# AUDIO_AMP.net
KiCad netlist of a schematic drawn in Altium Designer
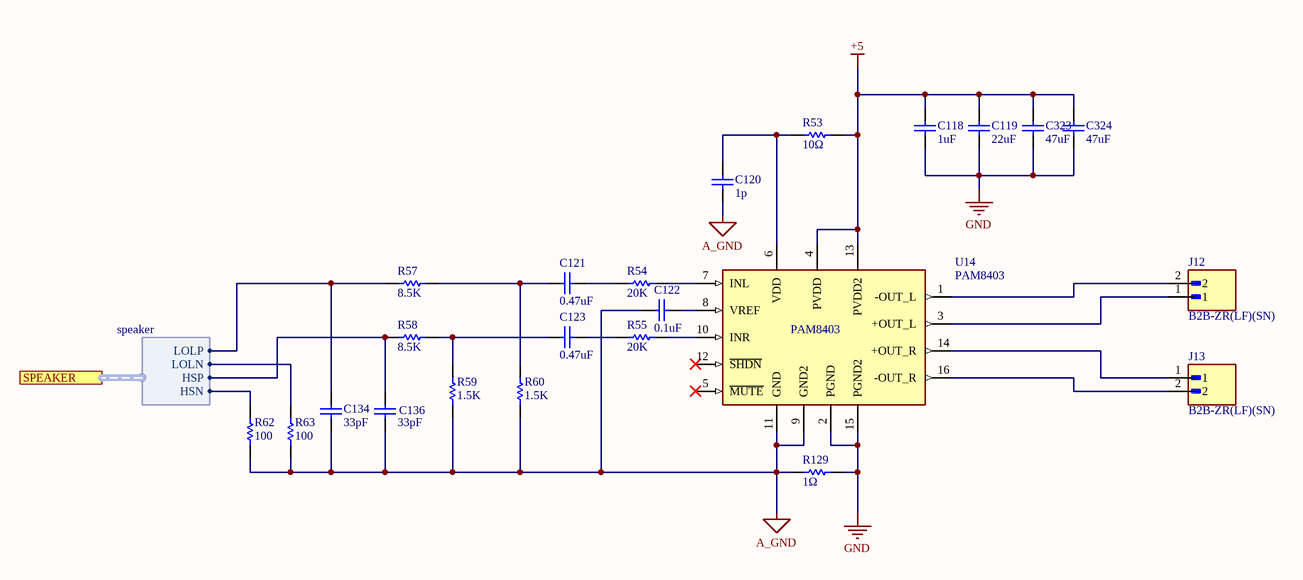
[diagram p0: AUDIO_AMP.SchDoc]

(export (version "E")
  (design (tool "Eeschema 10.0.6"))
  (components
    (comp (ref "C118")
      (value "1uF")
      (footprint "C0805")
      (fields (field (name "Comment") "C0805"))
      (libsource (lib "kit") (part "C0805"))
    )
    (comp (ref "C119")
      (value "22uF")
      (footprint "C1210")
      (fields (field (name "Comment") "C1210"))
      (libsource (lib "kit") (part "C1210"))
    )
    (comp (ref "C120")
      (value "1p")
      (footprint "C0402")
      (fields (field (name "Comment") "C0402"))
      (libsource (lib "kit") (part "C0402"))
    )
    (comp (ref "C121")
      (value "0.47uF")
      (footprint "C0603")
      (fields (field (name "Comment") "C0603"))
      (libsource (lib "kit") (part "C0603"))
    )
    (comp (ref "C122")
      (value "0.1uF")
      (footprint "C0603")
      (fields (field (name "Comment") "C0603"))
      (libsource (lib "kit") (part "C0603"))
    )
    (comp (ref "C123")
      (value "0.47uF")
      (footprint "C0603")
      (fields (field (name "Comment") "C0603"))
      (libsource (lib "kit") (part "C0603"))
    )
    (comp (ref "C134")
      (value "33pF")
      (footprint "C0402")
      (fields (field (name "Comment") "C0402"))
      (libsource (lib "kit") (part "C0402"))
    )
    (comp (ref "C136")
      (value "33pF")
      (footprint "C0402")
      (fields (field (name "Comment") "C0402"))
      (libsource (lib "kit") (part "C0402"))
    )
    (comp (ref "C323")
      (value "47uF")
      (footprint "C1812")
      (fields (field (name "Comment") "C1812"))
      (libsource (lib "kit") (part "C1812"))
    )
    (comp (ref "C324")
      (value "47uF")
      (footprint "C1812")
      (fields (field (name "Comment") "C1812"))
      (libsource (lib "kit") (part "C1812"))
    )
    (comp (ref "J12")
      (value "B2B-ZR(LF)(SN)")
      (footprint "JST_B2B-ZR(LF)(SN)")
      (description "Connector Header Through Hole 2 position 0.059 (1.50mm)")
      (libsource (lib "kit") (part "B2B-ZR(LF)(SN)"))
    )
    (comp (ref "J13")
      (value "B2B-ZR(LF)(SN)")
      (footprint "JST_B2B-ZR(LF)(SN)")
      (description "Connector Header Through Hole 2 position 0.059 (1.50mm)")
      (libsource (lib "") (part "B2B-ZR(LF)(SN)_1"))
    )
    (comp (ref "R53")
      (value "10Ω")
      (footprint "R0603")
      (fields (field (name "Comment") "R0603"))
      (libsource (lib "kit") (part "R0603"))
    )
    (comp (ref "R54")
      (value "20K")
      (footprint "R0603")
      (fields (field (name "Comment") "R0603"))
      (libsource (lib "kit") (part "R0603"))
    )
    (comp (ref "R55")
      (value "20K")
      (footprint "R0603")
      (fields (field (name "Comment") "R0603"))
      (libsource (lib "kit") (part "R0603"))
    )
    (comp (ref "R57")
      (value "8.5K")
      (footprint "R0603")
      (fields (field (name "Comment") "R0603"))
      (libsource (lib "kit") (part "R0603"))
    )
    (comp (ref "R58")
      (value "8.5K")
      (footprint "R0603")
      (fields (field (name "Comment") "R0603"))
      (libsource (lib "kit") (part "R0603"))
    )
    (comp (ref "R59")
      (value "1.5K")
      (footprint "R0603")
      (fields (field (name "Comment") "R0603"))
      (libsource (lib "kit") (part "R0603"))
    )
    (comp (ref "R60")
      (value "1.5K")
      (footprint "R0603")
      (fields (field (name "Comment") "R0603"))
      (libsource (lib "kit") (part "R0603"))
    )
    (comp (ref "R62")
      (value "100")
      (footprint "R0603")
      (fields (field (name "Comment") "R0603"))
      (libsource (lib "kit") (part "R0603"))
    )
    (comp (ref "R63")
      (value "100")
      (footprint "R0603")
      (fields (field (name "Comment") "R0603"))
      (libsource (lib "kit") (part "R0603"))
    )
    (comp (ref "R129")
      (value "1Ω")
      (footprint "R0603")
      (fields (field (name "Comment") "R0603"))
      (libsource (lib "kit") (part "R0603"))
    )
    (comp (ref "U14")
      (value "PAM8403")
      (footprint "SOP-16")
      (description "Audio Amp Speaker 2-CH Stereo 3.2W Class-D 16-Pin SOP T/R")
      (libsource (lib "kit") (part "PAM8403"))
    )
  )
  (nets
    (net (code "2") (name "+5") (class "Default")
      (node (ref "C118") (pin "1") (pinfunction "1_1") (pintype "passive"))
      (node (ref "C119") (pin "2") (pinfunction "2_2") (pintype "passive"))
      (node (ref "C323") (pin "2") (pinfunction "2_2") (pintype "passive"))
      (node (ref "C324") (pin "2") (pinfunction "2_2") (pintype "passive"))
      (node (ref "R53") (pin "2") (pinfunction "2_2") (pintype "passive"))
      (node (ref "U14") (pin "13") (pinfunction "PVDD2_13") (pintype "power_in"))
      (node (ref "U14") (pin "4") (pinfunction "PVDD_4") (pintype "power_in"))
    )
    (net (code "3") (name "/HSN") (class "Default")
      (node (ref "R62") (pin "2") (pinfunction "2_2") (pintype "passive"))
    )
    (net (code "4") (name "/HSP") (class "Default")
      (node (ref "C136") (pin "2") (pinfunction "2_2") (pintype "passive"))
      (node (ref "R58") (pin "1") (pinfunction "1_1") (pintype "passive"))
    )
    (net (code "5") (name "/LOLN") (class "Default")
      (node (ref "R63") (pin "2") (pinfunction "2_2") (pintype "passive"))
    )
    (net (code "6") (name "/LOLP") (class "Default")
      (node (ref "C134") (pin "2") (pinfunction "2_2") (pintype "passive"))
      (node (ref "R57") (pin "1") (pinfunction "1_1") (pintype "passive"))
    )
    (net (code "8") (name "A_GND") (class "Default")
      (node (ref "C120") (pin "1") (pinfunction "1_1") (pintype "passive"))
      (node (ref "C122") (pin "2") (pinfunction "2_2") (pintype "passive"))
      (node (ref "C134") (pin "1") (pinfunction "1_1") (pintype "passive"))
      (node (ref "C136") (pin "1") (pinfunction "1_1") (pintype "passive"))
      (node (ref "R129") (pin "1") (pinfunction "1_1") (pintype "passive"))
      (node (ref "R59") (pin "1") (pinfunction "1_1") (pintype "passive"))
      (node (ref "R60") (pin "1") (pinfunction "1_1") (pintype "passive"))
      (node (ref "R62") (pin "1") (pinfunction "1_1") (pintype "passive"))
      (node (ref "R63") (pin "1") (pinfunction "1_1") (pintype "passive"))
      (node (ref "U14") (pin "11") (pinfunction "GND_11") (pintype "power_in"))
      (node (ref "U14") (pin "9") (pinfunction "GND2_9") (pintype "power_in"))
    )
    (net (code "9") (name "GND") (class "Default")
      (node (ref "C118") (pin "2") (pinfunction "2_2") (pintype "passive"))
      (node (ref "C119") (pin "1") (pinfunction "1_1") (pintype "passive"))
      (node (ref "C323") (pin "1") (pinfunction "1_1") (pintype "passive"))
      (node (ref "C324") (pin "1") (pinfunction "1_1") (pintype "passive"))
      (node (ref "R129") (pin "2") (pinfunction "2_2") (pintype "passive"))
      (node (ref "U14") (pin "15") (pinfunction "PGND2_15") (pintype "power_in"))
      (node (ref "U14") (pin "2") (pinfunction "PGND_2") (pintype "power_in"))
    )
    (net (code "10") (name "Net-(C121-Pad1)") (class "Default")
      (node (ref "C121") (pin "1") (pinfunction "1_1") (pintype "passive"))
      (node (ref "R54") (pin "1") (pinfunction "1_1") (pintype "passive"))
    )
    (net (code "11") (name "Net-(C121-Pad2)") (class "Default")
      (node (ref "C121") (pin "2") (pinfunction "2_2") (pintype "passive"))
      (node (ref "R57") (pin "2") (pinfunction "2_2") (pintype "passive"))
      (node (ref "R60") (pin "2") (pinfunction "2_2") (pintype "passive"))
    )
    (net (code "12") (name "Net-(C123-Pad1)") (class "Default")
      (node (ref "C123") (pin "1") (pinfunction "1_1") (pintype "passive"))
      (node (ref "R55") (pin "1") (pinfunction "1_1") (pintype "passive"))
    )
    (net (code "13") (name "Net-(C123-Pad2)") (class "Default")
      (node (ref "C123") (pin "2") (pinfunction "2_2") (pintype "passive"))
      (node (ref "R58") (pin "2") (pinfunction "2_2") (pintype "passive"))
      (node (ref "R59") (pin "2") (pinfunction "2_2") (pintype "passive"))
    )
    (net (code "14") (name "Net-(U14-+OUT_L)") (class "Default")
      (node (ref "J12") (pin "1") (pinfunction "1_1") (pintype "passive"))
      (node (ref "U14") (pin "3") (pinfunction "+OUT_L_3") (pintype "output"))
    )
    (net (code "15") (name "Net-(U14-+OUT_R)") (class "Default")
      (node (ref "J13") (pin "1") (pinfunction "1_1") (pintype "passive"))
      (node (ref "U14") (pin "14") (pinfunction "+OUT_R_14") (pintype "output"))
    )
    (net (code "16") (name "Net-(U14--OUT_L)") (class "Default")
      (node (ref "J12") (pin "2") (pinfunction "2_2") (pintype "passive"))
      (node (ref "U14") (pin "1") (pinfunction "-OUT_L_1") (pintype "output"))
    )
    (net (code "17") (name "Net-(U14--OUT_R)") (class "Default")
      (node (ref "J13") (pin "2") (pinfunction "2_2") (pintype "passive"))
      (node (ref "U14") (pin "16") (pinfunction "-OUT_R_16") (pintype "output"))
    )
    (net (code "18") (name "Net-(U14-INL)") (class "Default")
      (node (ref "R54") (pin "2") (pinfunction "2_2") (pintype "passive"))
      (node (ref "U14") (pin "7") (pinfunction "INL_7") (pintype "input"))
    )
    (net (code "19") (name "Net-(U14-INR)") (class "Default")
      (node (ref "R55") (pin "2") (pinfunction "2_2") (pintype "passive"))
      (node (ref "U14") (pin "10") (pinfunction "INR_10") (pintype "input"))
    )
    (net (code "20") (name "Net-(U14-VDD)") (class "Default")
      (node (ref "C120") (pin "2") (pinfunction "2_2") (pintype "passive"))
      (node (ref "R53") (pin "1") (pinfunction "1_1") (pintype "passive"))
      (node (ref "U14") (pin "6") (pinfunction "VDD_6") (pintype "power_in"))
    )
    (net (code "21") (name "Net-(U14-VREF)") (class "Default")
      (node (ref "C122") (pin "1") (pinfunction "1_1") (pintype "passive"))
      (node (ref "U14") (pin "8") (pinfunction "VREF_8") (pintype "input"))
    )
    (net (code "22") (name "unconnected-(U14-~{MUTE}-Pad5)") (class "Default")
      (node (ref "U14") (pin "5") (pinfunction "~{MUTE}_5") (pintype "input+no_connect"))
    )
    (net (code "23") (name "unconnected-(U14-~{SHDN}-Pad12)") (class "Default")
      (node (ref "U14") (pin "12") (pinfunction "~{SHDN}_12") (pintype "input+no_connect"))
    )
  )
)
